# arduino_shield_v2.net
KiCad netlist of a schematic drawn in EAGLE
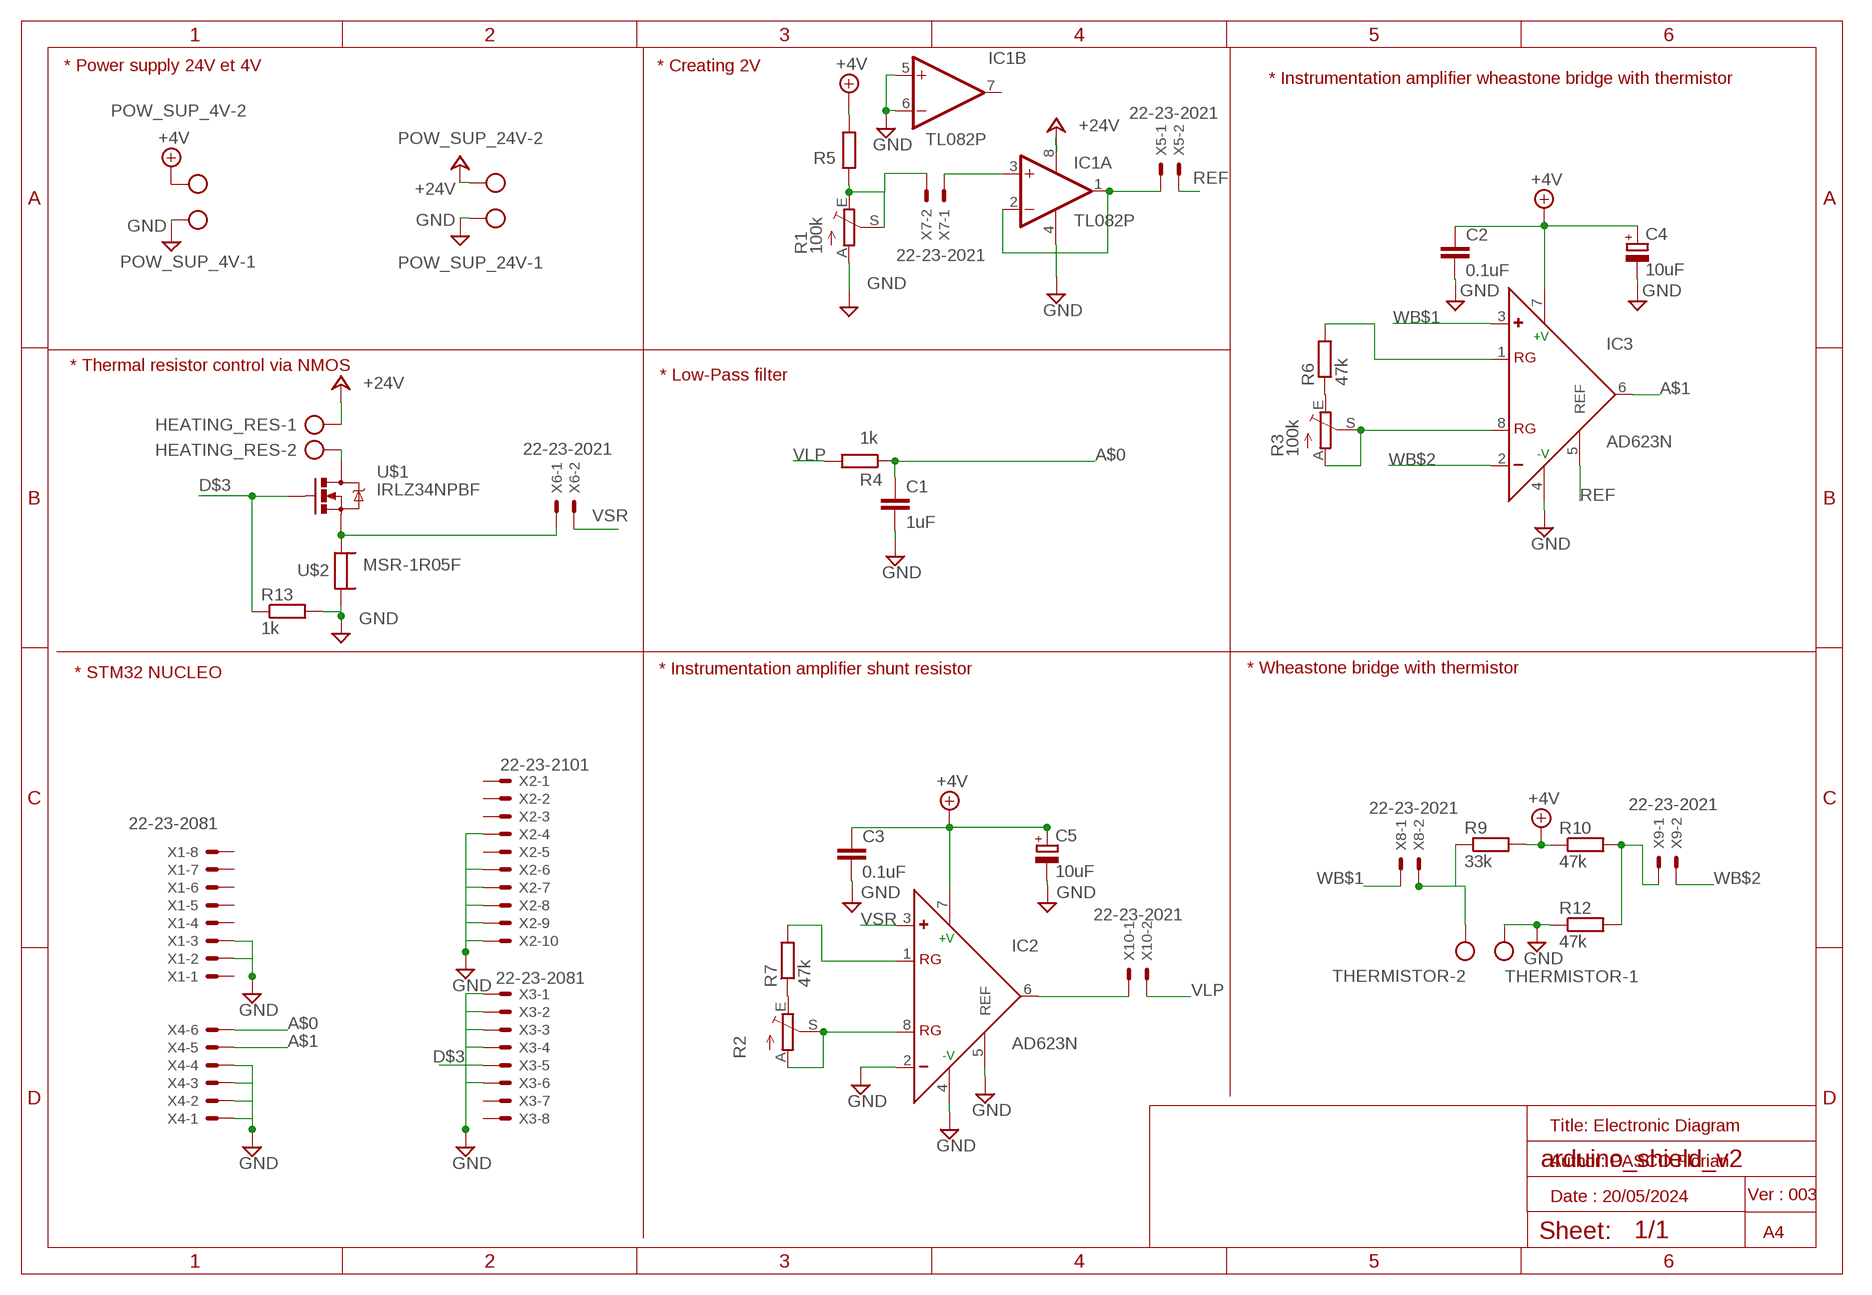
[diagram p0: schematic, sheet 1]

(export (version "E")
  (design (tool "Eeschema 10.0.6"))
  (components
    (comp (ref "C1")
      (value "1uF")
      (footprint "eagle-import:C050-025X075")
      (libsource (lib "eagle-import") (part "C-EU050-025X075"))
    )
    (comp (ref "C2")
      (value "0.1uF")
      (footprint "eagle-import:C050-025X075")
      (libsource (lib "eagle-import") (part "C-EU050-025X075"))
    )
    (comp (ref "C3")
      (value "0.1uF")
      (footprint "eagle-import:C050-025X075")
      (libsource (lib "eagle-import") (part "C-EU050-025X075"))
    )
    (comp (ref "C4")
      (value "10uF")
      (footprint "eagle-import:E5-5")
      (libsource (lib "eagle-import") (part "CPOL-EUE5-5"))
    )
    (comp (ref "C5")
      (value "10uF")
      (footprint "eagle-import:E5-5")
      (libsource (lib "eagle-import") (part "CPOL-EUE5-5"))
    )
    (comp (ref "HEATING_RES")
      (value "AK300/2")
      (footprint "eagle-import:AK300_2")
      (libsource (lib "eagle-import") (part "AK300/2"))
    )
    (comp (ref "IC1")
      (value "TL082P")
      (footprint "eagle-import:DIL08")
      (libsource (lib "eagle-import") (part "TL082P"))
    )
    (comp (ref "IC2")
      (value "AD623N")
      (footprint "eagle-import:DIL08")
      (fields (field (name "MF") "ALTERA CORPORATION") (field (name "MPN") "AD623ANZ"))
      (libsource (lib "eagle-import") (part "AD623N"))
    )
    (comp (ref "IC3")
      (value "AD623N")
      (footprint "eagle-import:DIL08")
      (fields (field (name "MF") "ALTERA CORPORATION") (field (name "MPN") "AD623ANZ"))
      (libsource (lib "eagle-import") (part "AD623N"))
    )
    (comp (ref "POW_SUP_4V")
      (value "AK300/2")
      (footprint "eagle-import:AK300_2")
      (libsource (lib "eagle-import") (part "AK300/2"))
    )
    (comp (ref "POW_SUP_24V")
      (value "AK300/2")
      (footprint "eagle-import:AK300_2")
      (libsource (lib "eagle-import") (part "AK300/2"))
    )
    (comp (ref "R1")
      (value "100k")
      (footprint "eagle-import:S64W")
      (libsource (lib "eagle-import") (part "TRIM_EU-S64W"))
    )
    (comp (ref "R2")
      (value "TRIM_EU-S64W")
      (footprint "eagle-import:S64W")
      (libsource (lib "eagle-import") (part "TRIM_EU-S64W"))
    )
    (comp (ref "R3")
      (value "100k")
      (footprint "eagle-import:S64W")
      (libsource (lib "eagle-import") (part "TRIM_EU-S64W"))
    )
    (comp (ref "R4")
      (value "1k")
      (footprint "eagle-import:0207_10")
      (libsource (lib "eagle-import") (part "R-EU_0207/10"))
    )
    (comp (ref "R5")
      (value "47k")
      (footprint "eagle-import:0207_10")
      (libsource (lib "eagle-import") (part "R-EU_0207/10"))
    )
    (comp (ref "R6")
      (value "47k")
      (footprint "eagle-import:0207_10")
      (libsource (lib "eagle-import") (part "R-EU_0207/10"))
    )
    (comp (ref "R7")
      (value "47k")
      (footprint "eagle-import:0207_10")
      (libsource (lib "eagle-import") (part "R-EU_0207/10"))
    )
    (comp (ref "R9")
      (value "33k")
      (footprint "eagle-import:0207_10")
      (libsource (lib "eagle-import") (part "R-EU_0207/10"))
    )
    (comp (ref "R10")
      (value "47k")
      (footprint "eagle-import:0207_10")
      (libsource (lib "eagle-import") (part "R-EU_0207/10"))
    )
    (comp (ref "R12")
      (value "47k")
      (footprint "eagle-import:0207_10")
      (libsource (lib "eagle-import") (part "R-EU_0207/10"))
    )
    (comp (ref "R13")
      (value "1k")
      (footprint "eagle-import:0207_10")
      (libsource (lib "eagle-import") (part "R-EU_0207/10"))
    )
    (comp (ref "THERMISTOR")
      (value "AK300/2")
      (footprint "eagle-import:AK300_2")
      (libsource (lib "eagle-import") (part "AK300/2"))
    )
    (comp (ref "U$1")
      (value "IRLZ34NPBF")
      (footprint "eagle-import:TO-220(2)")
      (fields (field (name "MF") "Infineon"))
      (libsource (lib "eagle-import") (part "IRLZ34NPBF"))
    )
    (comp (ref "U$2")
      (value "MSR-1R05F")
      (footprint "eagle-import:MSR1")
      (libsource (lib "eagle-import") (part "MSR-1R05F"))
    )
    (comp (ref "X1")
      (value "22-23-2081")
      (footprint "eagle-import:22-23-2081")
      (fields (field (name "MF") "MOLEX"))
      (libsource (lib "eagle-import") (part "22-23-2081"))
    )
    (comp (ref "X2")
      (value "22-23-2101")
      (footprint "eagle-import:22-23-2101")
      (fields (field (name "MF") "MOLEX"))
      (libsource (lib "eagle-import") (part "22-23-2101"))
    )
    (comp (ref "X3")
      (value "22-23-2081")
      (footprint "eagle-import:22-23-2081")
      (fields (field (name "MF") "MOLEX"))
      (libsource (lib "eagle-import") (part "22-23-2081"))
    )
    (comp (ref "X4")
      (value "22-23-2061")
      (footprint "eagle-import:22-23-2061")
      (fields (field (name "MF") "MOLEX"))
      (libsource (lib "eagle-import") (part "22-23-2061"))
    )
    (comp (ref "X5")
      (value "22-23-2021")
      (footprint "eagle-import:22-23-2021")
      (fields (field (name "MF") "MOLEX"))
      (libsource (lib "eagle-import") (part "22-23-2021"))
    )
    (comp (ref "X6")
      (value "22-23-2021")
      (footprint "eagle-import:22-23-2021")
      (fields (field (name "MF") "MOLEX"))
      (libsource (lib "eagle-import") (part "22-23-2021"))
    )
    (comp (ref "X7")
      (value "22-23-2021")
      (footprint "eagle-import:22-23-2021")
      (fields (field (name "MF") "MOLEX"))
      (libsource (lib "eagle-import") (part "22-23-2021"))
    )
    (comp (ref "X8")
      (value "22-23-2021")
      (footprint "eagle-import:22-23-2021")
      (fields (field (name "MF") "MOLEX"))
      (libsource (lib "eagle-import") (part "22-23-2021"))
    )
    (comp (ref "X9")
      (value "22-23-2021")
      (footprint "eagle-import:22-23-2021")
      (fields (field (name "MF") "MOLEX"))
      (libsource (lib "eagle-import") (part "22-23-2021"))
    )
    (comp (ref "X10")
      (value "22-23-2021")
      (footprint "eagle-import:22-23-2021")
      (fields (field (name "MF") "MOLEX"))
      (libsource (lib "eagle-import") (part "22-23-2021"))
    )
  )
  (nets
    (net (code "1") (name "+4V") (class "Default")
      (node (ref "C2") (pin "1") (pinfunction "1_1") (pintype "passive"))
      (node (ref "C3") (pin "1") (pinfunction "1_1") (pintype "passive"))
      (node (ref "C4") (pin "+") (pinfunction "+_+") (pintype "passive"))
      (node (ref "C5") (pin "+") (pinfunction "+_+") (pintype "passive"))
      (node (ref "IC2") (pin "7") (pinfunction "+V_7") (pintype "power_in"))
      (node (ref "IC3") (pin "7") (pinfunction "+V_7") (pintype "power_in"))
      (node (ref "POW_SUP_4V") (pin "2") (pinfunction "KL_2") (pintype "passive"))
      (node (ref "R10") (pin "1") (pinfunction "1_1") (pintype "passive"))
      (node (ref "R5") (pin "2") (pinfunction "2_2") (pintype "passive"))
      (node (ref "R9") (pin "2") (pinfunction "2_2") (pintype "passive"))
    )
    (net (code "2") (name "+24V") (class "Default")
      (node (ref "HEATING_RES") (pin "1") (pinfunction "KL_1") (pintype "passive"))
      (node (ref "IC1") (pin "8") (pinfunction "V+_8") (pintype "power_in"))
      (node (ref "POW_SUP_24V") (pin "2") (pinfunction "KL_2") (pintype "passive"))
    )
    (net (code "3") (name "/A$0") (class "Default")
      (node (ref "C1") (pin "1") (pinfunction "1_1") (pintype "passive"))
      (node (ref "R4") (pin "1") (pinfunction "1_1") (pintype "passive"))
      (node (ref "X4") (pin "6") (pinfunction "S_6") (pintype "passive"))
    )
    (net (code "4") (name "/A$1") (class "Default")
      (node (ref "IC3") (pin "6") (pinfunction "OUT_6") (pintype "output"))
      (node (ref "X4") (pin "5") (pinfunction "S_5") (pintype "passive"))
    )
    (net (code "5") (name "/D$3") (class "Default")
      (node (ref "R13") (pin "1") (pinfunction "1_1") (pintype "passive"))
      (node (ref "U$1") (pin "IN") (pinfunction "G_IN") (pintype "passive"))
      (node (ref "X3") (pin "5") (pinfunction "S_5") (pintype "passive"))
    )
    (net (code "6") (name "/REF") (class "Default")
      (node (ref "IC3") (pin "5") (pinfunction "REF_5") (pintype "passive"))
      (node (ref "X5") (pin "2") (pinfunction "S_2") (pintype "passive"))
    )
    (net (code "7") (name "/VLP") (class "Default")
      (node (ref "R4") (pin "2") (pinfunction "2_2") (pintype "passive"))
      (node (ref "X10") (pin "2") (pinfunction "S_2") (pintype "passive"))
    )
    (net (code "8") (name "/VSR") (class "Default")
      (node (ref "IC2") (pin "3") (pinfunction "+_3") (pintype "input"))
      (node (ref "X6") (pin "2") (pinfunction "S_2") (pintype "passive"))
    )
    (net (code "9") (name "/WB$1") (class "Default")
      (node (ref "IC3") (pin "3") (pinfunction "+_3") (pintype "input"))
      (node (ref "X8") (pin "1") (pinfunction "S_1") (pintype "passive"))
    )
    (net (code "10") (name "/WB$2") (class "Default")
      (node (ref "IC3") (pin "2") (pinfunction "-_2") (pintype "input"))
      (node (ref "X9") (pin "2") (pinfunction "S_2") (pintype "passive"))
    )
    (net (code "11") (name "GND") (class "Default")
      (node (ref "C1") (pin "2") (pinfunction "2_2") (pintype "passive"))
      (node (ref "C2") (pin "2") (pinfunction "2_2") (pintype "passive"))
      (node (ref "C3") (pin "2") (pinfunction "2_2") (pintype "passive"))
      (node (ref "C4") (pin "-") (pinfunction "-_-") (pintype "passive"))
      (node (ref "C5") (pin "-") (pinfunction "-_-") (pintype "passive"))
      (node (ref "IC1") (pin "4") (pinfunction "V-_4") (pintype "power_in"))
      (node (ref "IC1") (pin "5") (pinfunction "+IN_5") (pintype "input"))
      (node (ref "IC1") (pin "6") (pinfunction "-IN_6") (pintype "input"))
      (node (ref "IC2") (pin "2") (pinfunction "-_2") (pintype "input"))
      (node (ref "IC2") (pin "4") (pinfunction "-V_4") (pintype "power_in"))
      (node (ref "IC2") (pin "5") (pinfunction "REF_5") (pintype "passive"))
      (node (ref "IC3") (pin "4") (pinfunction "-V_4") (pintype "power_in"))
      (node (ref "POW_SUP_24V") (pin "1") (pinfunction "KL_1") (pintype "passive"))
      (node (ref "POW_SUP_4V") (pin "1") (pinfunction "KL_1") (pintype "passive"))
      (node (ref "R1") (pin "A") (pinfunction "A_A") (pintype "passive"))
      (node (ref "R12") (pin "1") (pinfunction "1_1") (pintype "passive"))
      (node (ref "R13") (pin "2") (pinfunction "2_2") (pintype "passive"))
      (node (ref "THERMISTOR") (pin "1") (pinfunction "KL_1") (pintype "passive"))
      (node (ref "U$2") (pin "P$2") (pinfunction "2_P$2") (pintype "passive"))
      (node (ref "X1") (pin "2") (pinfunction "S_2") (pintype "passive"))
      (node (ref "X1") (pin "3") (pinfunction "S_3") (pintype "passive"))
      (node (ref "X2") (pin "10") (pinfunction "S_10") (pintype "passive"))
      (node (ref "X2") (pin "4") (pinfunction "S_4") (pintype "passive"))
      (node (ref "X2") (pin "6") (pinfunction "S_6") (pintype "passive"))
      (node (ref "X2") (pin "7") (pinfunction "S_7") (pintype "passive"))
      (node (ref "X2") (pin "8") (pinfunction "S_8") (pintype "passive"))
      (node (ref "X2") (pin "9") (pinfunction "S_9") (pintype "passive"))
      (node (ref "X3") (pin "1") (pinfunction "S_1") (pintype "passive"))
      (node (ref "X3") (pin "2") (pinfunction "S_2") (pintype "passive"))
      (node (ref "X3") (pin "3") (pinfunction "S_3") (pintype "passive"))
      (node (ref "X3") (pin "4") (pinfunction "S_4") (pintype "passive"))
      (node (ref "X3") (pin "6") (pinfunction "S_6") (pintype "passive"))
      (node (ref "X4") (pin "1") (pinfunction "S_1") (pintype "passive"))
      (node (ref "X4") (pin "2") (pinfunction "S_2") (pintype "passive"))
      (node (ref "X4") (pin "3") (pinfunction "S_3") (pintype "passive"))
      (node (ref "X4") (pin "4") (pinfunction "S_4") (pintype "passive"))
    )
    (net (code "12") (name "Net-(HEATING_RESB-KL)") (class "Default")
      (node (ref "HEATING_RES") (pin "2") (pinfunction "KL_2") (pintype "passive"))
      (node (ref "U$1") (pin "GND") (pinfunction "D_GND") (pintype "passive"))
    )
    (net (code "13") (name "Net-(IC1A-+IN)") (class "Default")
      (node (ref "IC1") (pin "3") (pinfunction "+IN_3") (pintype "input"))
      (node (ref "X7") (pin "1") (pinfunction "S_1") (pintype "passive"))
    )
    (net (code "14") (name "Net-(IC1A--IN)") (class "Default")
      (node (ref "IC1") (pin "1") (pinfunction "OUT_1") (pintype "output"))
      (node (ref "IC1") (pin "2") (pinfunction "-IN_2") (pintype "input"))
      (node (ref "X5") (pin "1") (pinfunction "S_1") (pintype "passive"))
    )
    (net (code "15") (name "Net-(IC2-OUT)") (class "Default")
      (node (ref "IC2") (pin "6") (pinfunction "OUT_6") (pintype "output"))
      (node (ref "X10") (pin "1") (pinfunction "S_1") (pintype "passive"))
    )
    (net (code "16") (name "Net-(IC2-RG-Pad1)") (class "Default")
      (node (ref "IC2") (pin "1") (pinfunction "RG_1") (pintype "passive"))
      (node (ref "R7") (pin "2") (pinfunction "2_2") (pintype "passive"))
    )
    (net (code "17") (name "Net-(IC2-RG-Pad8)") (class "Default")
      (node (ref "IC2") (pin "8") (pinfunction "RG_8") (pintype "passive"))
      (node (ref "R2") (pin "A") (pinfunction "A_A") (pintype "passive"))
      (node (ref "R2") (pin "S") (pinfunction "S_S") (pintype "passive"))
    )
    (net (code "18") (name "Net-(IC3-RG-Pad1)") (class "Default")
      (node (ref "IC3") (pin "1") (pinfunction "RG_1") (pintype "passive"))
      (node (ref "R6") (pin "2") (pinfunction "2_2") (pintype "passive"))
    )
    (net (code "19") (name "Net-(IC3-RG-Pad8)") (class "Default")
      (node (ref "IC3") (pin "8") (pinfunction "RG_8") (pintype "passive"))
      (node (ref "R3") (pin "A") (pinfunction "A_A") (pintype "passive"))
      (node (ref "R3") (pin "S") (pinfunction "S_S") (pintype "passive"))
    )
    (net (code "20") (name "Net-(R2-PadE)") (class "Default")
      (node (ref "R2") (pin "E") (pinfunction "E_E") (pintype "passive"))
      (node (ref "R7") (pin "1") (pinfunction "1_1") (pintype "passive"))
    )
    (net (code "21") (name "Net-(R3-PadE)") (class "Default")
      (node (ref "R3") (pin "E") (pinfunction "E_E") (pintype "passive"))
      (node (ref "R6") (pin "1") (pinfunction "1_1") (pintype "passive"))
    )
    (net (code "22") (name "Net-(THERMISTORB-KL)") (class "Default")
      (node (ref "R9") (pin "1") (pinfunction "1_1") (pintype "passive"))
      (node (ref "THERMISTOR") (pin "2") (pinfunction "KL_2") (pintype "passive"))
      (node (ref "X8") (pin "2") (pinfunction "S_2") (pintype "passive"))
    )
    (net (code "23") (name "Net-(U$1-S)") (class "Default")
      (node (ref "U$1") (pin "OUT") (pinfunction "S_OUT") (pintype "passive"))
      (node (ref "U$2") (pin "P$1") (pinfunction "1_P$1") (pintype "passive"))
      (node (ref "X6") (pin "1") (pinfunction "S_1") (pintype "passive"))
    )
    (net (code "24") (name "Net-(X7B-S)") (class "Default")
      (node (ref "R1") (pin "E") (pinfunction "E_E") (pintype "passive"))
      (node (ref "R1") (pin "S") (pinfunction "S_S") (pintype "passive"))
      (node (ref "R5") (pin "1") (pinfunction "1_1") (pintype "passive"))
      (node (ref "X7") (pin "2") (pinfunction "S_2") (pintype "passive"))
    )
    (net (code "25") (name "Net-(X9A-S)") (class "Default")
      (node (ref "R10") (pin "2") (pinfunction "2_2") (pintype "passive"))
      (node (ref "R12") (pin "2") (pinfunction "2_2") (pintype "passive"))
      (node (ref "X9") (pin "1") (pinfunction "S_1") (pintype "passive"))
    )
    (net (code "26") (name "unconnected-(IC1B-OUT-Pad7)") (class "Default")
      (node (ref "IC1") (pin "7") (pinfunction "OUT_7") (pintype "output"))
    )
    (net (code "27") (name "unconnected-(X1A-S-Pad1)") (class "Default")
      (node (ref "X1") (pin "1") (pinfunction "S_1") (pintype "passive"))
    )
    (net (code "28") (name "unconnected-(X1D-S-Pad4)") (class "Default")
      (node (ref "X1") (pin "4") (pinfunction "S_4") (pintype "passive"))
    )
    (net (code "29") (name "unconnected-(X1E-S-Pad5)") (class "Default")
      (node (ref "X1") (pin "5") (pinfunction "S_5") (pintype "passive"))
    )
    (net (code "30") (name "unconnected-(X1F-S-Pad6)") (class "Default")
      (node (ref "X1") (pin "6") (pinfunction "S_6") (pintype "passive"))
    )
    (net (code "31") (name "unconnected-(X1G-S-Pad7)") (class "Default")
      (node (ref "X1") (pin "7") (pinfunction "S_7") (pintype "passive"))
    )
    (net (code "32") (name "unconnected-(X1H-S-Pad8)") (class "Default")
      (node (ref "X1") (pin "8") (pinfunction "S_8") (pintype "passive"))
    )
    (net (code "33") (name "unconnected-(X2A-S-Pad1)") (class "Default")
      (node (ref "X2") (pin "1") (pinfunction "S_1") (pintype "passive"))
    )
    (net (code "34") (name "unconnected-(X2C-S-Pad2)") (class "Default")
      (node (ref "X2") (pin "2") (pinfunction "S_2") (pintype "passive"))
    )
    (net (code "35") (name "unconnected-(X2D-S-Pad3)") (class "Default")
      (node (ref "X2") (pin "3") (pinfunction "S_3") (pintype "passive"))
    )
    (net (code "36") (name "unconnected-(X2F-S-Pad5)") (class "Default")
      (node (ref "X2") (pin "5") (pinfunction "S_5") (pintype "passive"))
    )
    (net (code "37") (name "unconnected-(X3G-S-Pad7)") (class "Default")
      (node (ref "X3") (pin "7") (pinfunction "S_7") (pintype "passive"))
    )
    (net (code "38") (name "unconnected-(X3H-S-Pad8)") (class "Default")
      (node (ref "X3") (pin "8") (pinfunction "S_8") (pintype "passive"))
    )
  )
)
